# snes_visualization_right.net
KiCad netlist of a schematic drawn in EAGLE
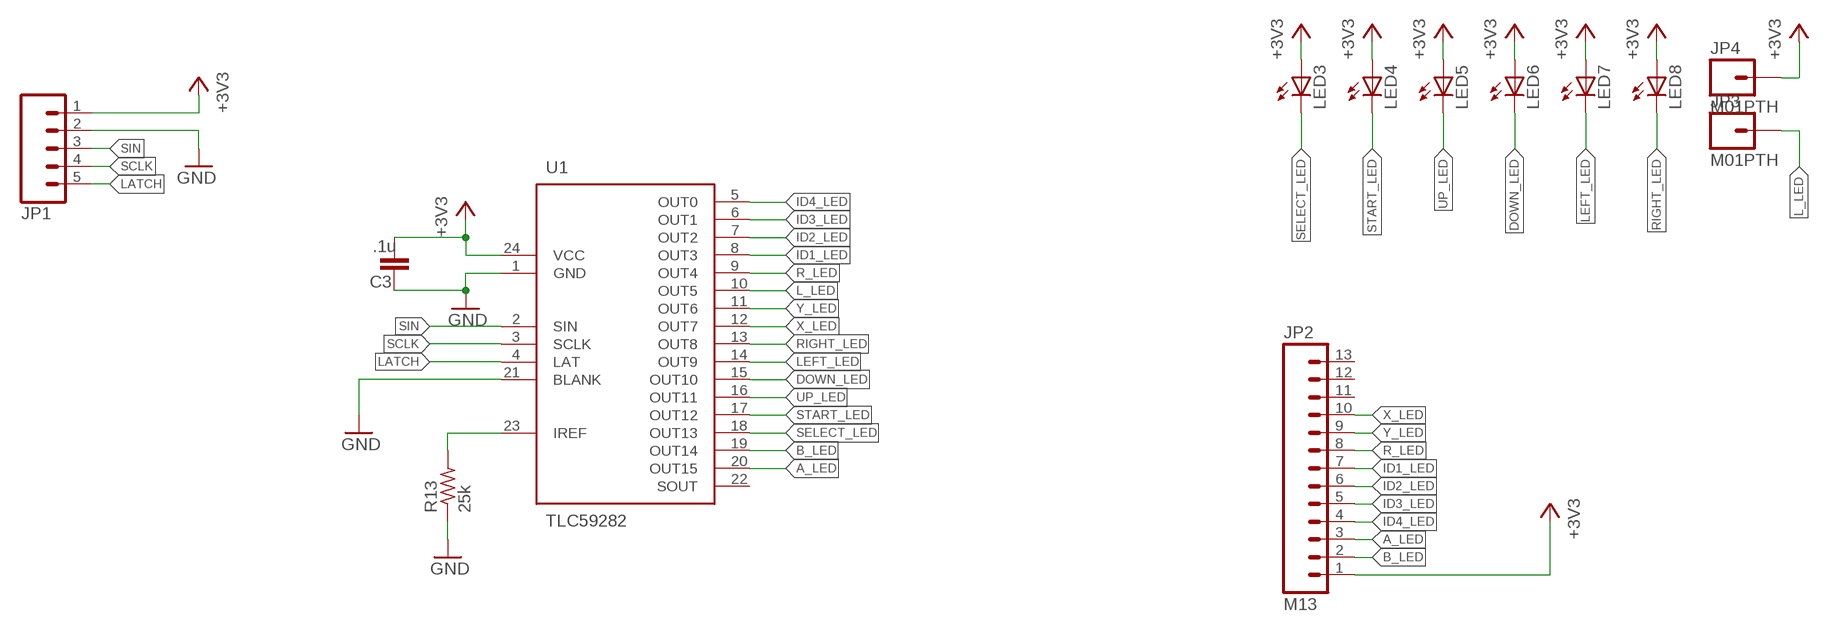
[diagram p0: schematic, sheet 1]

(export (version "E")
  (design (tool "Eeschema 10.0.6"))
  (components
    (comp (ref "C3")
      (value ".1u")
      (footprint "eagle-import:C0603")
      (libsource (lib "eagle-import") (part "C-EUC0603"))
    )
    (comp (ref "JP1")
      (value "M05PTH")
      (footprint "eagle-import:1X05")
      (libsource (lib "eagle-import") (part "M05PTH"))
    )
    (comp (ref "JP2")
      (value "M13")
      (footprint "eagle-import:1X13")
      (libsource (lib "eagle-import") (part "M13"))
    )
    (comp (ref "JP3")
      (value "M01PTH")
      (footprint "eagle-import:1X01")
      (libsource (lib "eagle-import") (part "M01PTH"))
    )
    (comp (ref "JP4")
      (value "M01PTH")
      (footprint "eagle-import:1X01")
      (libsource (lib "eagle-import") (part "M01PTH"))
    )
    (comp (ref "LED3")
      (value "LED3MM")
      (footprint "eagle-import:LED3MM")
      (libsource (lib "eagle-import") (part "LED3MM"))
    )
    (comp (ref "LED4")
      (value "LED3MM")
      (footprint "eagle-import:LED3MM")
      (libsource (lib "eagle-import") (part "LED3MM"))
    )
    (comp (ref "LED5")
      (value "LED5MM")
      (footprint "eagle-import:LED5MM")
      (libsource (lib "eagle-import") (part "LED5MM"))
    )
    (comp (ref "LED6")
      (value "LED5MM")
      (footprint "eagle-import:LED5MM")
      (libsource (lib "eagle-import") (part "LED5MM"))
    )
    (comp (ref "LED7")
      (value "LED5MM")
      (footprint "eagle-import:LED5MM")
      (libsource (lib "eagle-import") (part "LED5MM"))
    )
    (comp (ref "LED8")
      (value "LED5MM")
      (footprint "eagle-import:LED5MM")
      (libsource (lib "eagle-import") (part "LED5MM"))
    )
    (comp (ref "R13")
      (value "25k")
      (footprint "eagle-import:R0805")
      (libsource (lib "eagle-import") (part "R-US_R0805"))
    )
    (comp (ref "U1")
      (value "TLC59282")
      (footprint "eagle-import:R-PDSO-G24")
      (libsource (lib "eagle-import") (part "TLC59282"))
    )
  )
  (nets
    (net (code "1") (name "+3V3") (class "Default")
      (node (ref "C3") (pin "1") (pinfunction "1_1") (pintype "passive"))
      (node (ref "JP1") (pin "1") (pinfunction "1_1") (pintype "passive"))
      (node (ref "JP2") (pin "1") (pinfunction "1_1") (pintype "passive"))
      (node (ref "JP4") (pin "1") (pinfunction "1_1") (pintype "passive"))
      (node (ref "LED3") (pin "A") (pinfunction "A_A") (pintype "passive"))
      (node (ref "LED4") (pin "A") (pinfunction "A_A") (pintype "passive"))
      (node (ref "LED5") (pin "A") (pinfunction "A_A") (pintype "passive"))
      (node (ref "LED6") (pin "A") (pinfunction "A_A") (pintype "passive"))
      (node (ref "LED7") (pin "A") (pinfunction "A_A") (pintype "passive"))
      (node (ref "LED8") (pin "A") (pinfunction "A_A") (pintype "passive"))
      (node (ref "U1") (pin "24") (pinfunction "VCC_24") (pintype "input"))
    )
    (net (code "2") (name "A_LED") (class "Default")
      (node (ref "JP2") (pin "3") (pinfunction "3_3") (pintype "passive"))
      (node (ref "U1") (pin "20") (pinfunction "OUT15_20") (pintype "input"))
    )
    (net (code "3") (name "B_LED") (class "Default")
      (node (ref "JP2") (pin "2") (pinfunction "2_2") (pintype "passive"))
      (node (ref "U1") (pin "19") (pinfunction "OUT14_19") (pintype "input"))
    )
    (net (code "4") (name "DOWN_LED") (class "Default")
      (node (ref "LED6") (pin "K") (pinfunction "C_K") (pintype "passive"))
      (node (ref "U1") (pin "15") (pinfunction "OUT10_15") (pintype "input"))
    )
    (net (code "5") (name "GND") (class "Default")
      (node (ref "C3") (pin "2") (pinfunction "2_2") (pintype "passive"))
      (node (ref "JP1") (pin "2") (pinfunction "2_2") (pintype "passive"))
      (node (ref "R13") (pin "1") (pinfunction "1_1") (pintype "passive"))
      (node (ref "U1") (pin "1") (pinfunction "GND_1") (pintype "input"))
      (node (ref "U1") (pin "21") (pinfunction "BLANK_21") (pintype "input"))
    )
    (net (code "6") (name "ID1_LED") (class "Default")
      (node (ref "JP2") (pin "7") (pinfunction "7_7") (pintype "passive"))
      (node (ref "U1") (pin "8") (pinfunction "OUT3_8") (pintype "input"))
    )
    (net (code "7") (name "ID2_LED") (class "Default")
      (node (ref "JP2") (pin "6") (pinfunction "6_6") (pintype "passive"))
      (node (ref "U1") (pin "7") (pinfunction "OUT2_7") (pintype "input"))
    )
    (net (code "8") (name "ID3_LED") (class "Default")
      (node (ref "JP2") (pin "5") (pinfunction "5_5") (pintype "passive"))
      (node (ref "U1") (pin "6") (pinfunction "OUT1_6") (pintype "input"))
    )
    (net (code "9") (name "ID4_LED") (class "Default")
      (node (ref "JP2") (pin "4") (pinfunction "4_4") (pintype "passive"))
      (node (ref "U1") (pin "5") (pinfunction "OUT0_5") (pintype "input"))
    )
    (net (code "10") (name "LATCH") (class "Default")
      (node (ref "JP1") (pin "5") (pinfunction "5_5") (pintype "passive"))
      (node (ref "U1") (pin "4") (pinfunction "LAT_4") (pintype "input"))
    )
    (net (code "11") (name "LEFT_LED") (class "Default")
      (node (ref "LED7") (pin "K") (pinfunction "C_K") (pintype "passive"))
      (node (ref "U1") (pin "14") (pinfunction "OUT9_14") (pintype "input"))
    )
    (net (code "12") (name "L_LED") (class "Default")
      (node (ref "JP3") (pin "1") (pinfunction "1_1") (pintype "passive"))
      (node (ref "U1") (pin "10") (pinfunction "OUT5_10") (pintype "input"))
    )
    (net (code "13") (name "Net-(U1-IREF)") (class "Default")
      (node (ref "R13") (pin "2") (pinfunction "2_2") (pintype "passive"))
      (node (ref "U1") (pin "23") (pinfunction "IREF_23") (pintype "input"))
    )
    (net (code "14") (name "RIGHT_LED") (class "Default")
      (node (ref "LED8") (pin "K") (pinfunction "C_K") (pintype "passive"))
      (node (ref "U1") (pin "13") (pinfunction "OUT8_13") (pintype "input"))
    )
    (net (code "15") (name "R_LED") (class "Default")
      (node (ref "JP2") (pin "8") (pinfunction "8_8") (pintype "passive"))
      (node (ref "U1") (pin "9") (pinfunction "OUT4_9") (pintype "input"))
    )
    (net (code "16") (name "SCLK") (class "Default")
      (node (ref "JP1") (pin "4") (pinfunction "4_4") (pintype "passive"))
      (node (ref "U1") (pin "3") (pinfunction "SCLK_3") (pintype "input"))
    )
    (net (code "17") (name "SELECT_LED") (class "Default")
      (node (ref "LED3") (pin "K") (pinfunction "C_K") (pintype "passive"))
      (node (ref "U1") (pin "18") (pinfunction "OUT13_18") (pintype "input"))
    )
    (net (code "18") (name "SIN") (class "Default")
      (node (ref "JP1") (pin "3") (pinfunction "3_3") (pintype "passive"))
      (node (ref "U1") (pin "2") (pinfunction "SIN_2") (pintype "input"))
    )
    (net (code "19") (name "START_LED") (class "Default")
      (node (ref "LED4") (pin "K") (pinfunction "C_K") (pintype "passive"))
      (node (ref "U1") (pin "17") (pinfunction "OUT12_17") (pintype "input"))
    )
    (net (code "20") (name "UP_LED") (class "Default")
      (node (ref "LED5") (pin "K") (pinfunction "C_K") (pintype "passive"))
      (node (ref "U1") (pin "16") (pinfunction "OUT11_16") (pintype "input"))
    )
    (net (code "21") (name "X_LED") (class "Default")
      (node (ref "JP2") (pin "10") (pinfunction "10_10") (pintype "passive"))
      (node (ref "U1") (pin "12") (pinfunction "OUT7_12") (pintype "input"))
    )
    (net (code "22") (name "Y_LED") (class "Default")
      (node (ref "JP2") (pin "9") (pinfunction "9_9") (pintype "passive"))
      (node (ref "U1") (pin "11") (pinfunction "OUT6_11") (pintype "input"))
    )
    (net (code "23") (name "unconnected-(JP2-Pad11)") (class "Default")
      (node (ref "JP2") (pin "11") (pinfunction "11_11") (pintype "passive"))
    )
    (net (code "24") (name "unconnected-(JP2-Pad12)") (class "Default")
      (node (ref "JP2") (pin "12") (pinfunction "12_12") (pintype "passive"))
    )
    (net (code "25") (name "unconnected-(JP2-Pad13)") (class "Default")
      (node (ref "JP2") (pin "13") (pinfunction "13_13") (pintype "passive"))
    )
    (net (code "26") (name "unconnected-(U1-SOUT-Pad22)") (class "Default")
      (node (ref "U1") (pin "22") (pinfunction "SOUT_22") (pintype "input"))
    )
  )
)
